# Dual-VCA.net
KiCad netlist of a schematic drawn in EAGLE
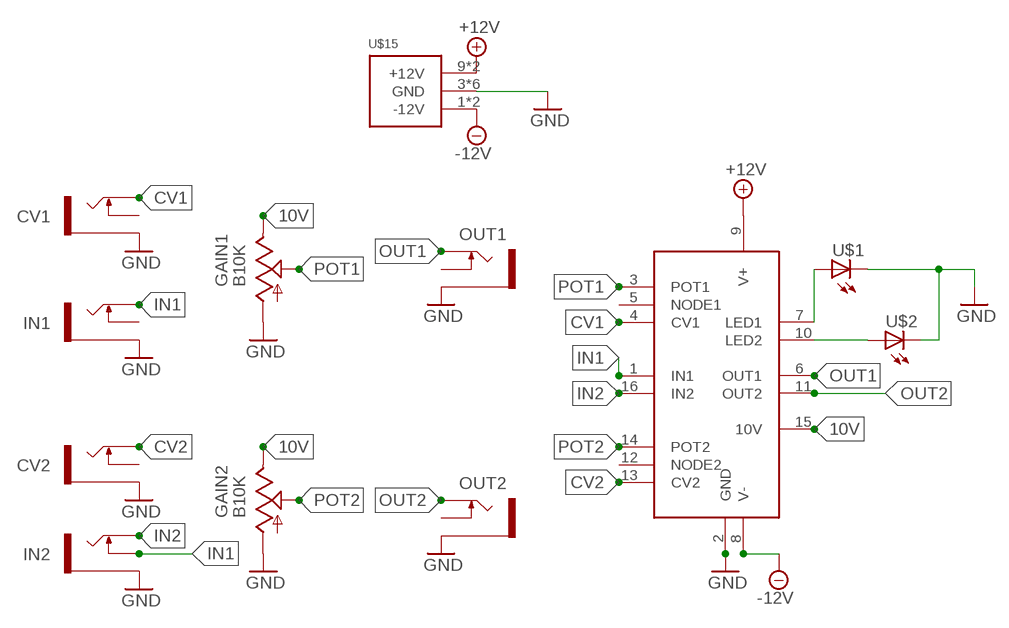
[diagram p0: schematic, sheet 1]

(export (version "E")
  (design (tool "Eeschema 10.0.6"))
  (components
    (comp (ref "CV1")
      (value "THONKICONN-SOCKETS-PJ301M-12NEW")
      (footprint "eagle-import:THONKICONN-SOCKETS-PJ301M-12")
      (fields (field (name "USE") "CV1"))
      (libsource (lib "eagle-import") (part "THONKICONN-SOCKETS-PJ301M-12NEW"))
    )
    (comp (ref "CV2")
      (value "THONKICONN-SOCKETS-PJ301M-12NEW")
      (footprint "eagle-import:THONKICONN-SOCKETS-PJ301M-12")
      (fields (field (name "USE") "CV2"))
      (libsource (lib "eagle-import") (part "THONKICONN-SOCKETS-PJ301M-12NEW"))
    )
    (comp (ref "GAIN1")
      (value "B10K")
      (footprint "eagle-import:MUSICTHINGMODULAR_9MM_SNAP-IN_POT")
      (libsource (lib "eagle-import") (part "MUSICTHINGMODULAR_9MM_SNAP-IN_POT_"))
    )
    (comp (ref "GAIN2")
      (value "B10K")
      (footprint "eagle-import:MUSICTHINGMODULAR_9MM_SNAP-IN_POT")
      (libsource (lib "eagle-import") (part "MUSICTHINGMODULAR_9MM_SNAP-IN_POT_"))
    )
    (comp (ref "IN1")
      (value "THONKICONN-SOCKETS-PJ301M-12NEW")
      (footprint "eagle-import:THONKICONN-SOCKETS-PJ301M-12")
      (fields (field (name "USE") "IN1"))
      (libsource (lib "eagle-import") (part "THONKICONN-SOCKETS-PJ301M-12NEW"))
    )
    (comp (ref "IN2")
      (value "THONKICONN-SOCKETS-PJ301M-12NEW")
      (footprint "eagle-import:THONKICONN-SOCKETS-PJ301M-12")
      (fields (field (name "USE") "IN2"))
      (libsource (lib "eagle-import") (part "THONKICONN-SOCKETS-PJ301M-12NEW"))
    )
    (comp (ref "OUT1")
      (value "THONKICONN-SOCKETS-PJ301M-12NEW")
      (footprint "eagle-import:THONKICONN-SOCKETS-PJ301M-12")
      (fields (field (name "USE") "OUT1"))
      (libsource (lib "eagle-import") (part "THONKICONN-SOCKETS-PJ301M-12NEW"))
    )
    (comp (ref "OUT2")
      (value "THONKICONN-SOCKETS-PJ301M-12NEW")
      (footprint "eagle-import:THONKICONN-SOCKETS-PJ301M-12")
      (fields (field (name "USE") "OUT2"))
      (libsource (lib "eagle-import") (part "THONKICONN-SOCKETS-PJ301M-12NEW"))
    )
    (comp (ref "U$1")
      (value "LED3MM")
      (footprint "eagle-import:LED3MM")
      (libsource (lib "eagle-import") (part "LED3MM"))
    )
    (comp (ref "U$2")
      (value "LED3MM")
      (footprint "eagle-import:LED3MM")
      (libsource (lib "eagle-import") (part "LED3MM"))
    )
    (comp (ref "U$15")
      (value "POWER_SIMPLE10")
      (footprint "eagle-import:POWER_10")
      (libsource (lib "eagle-import") (part "POWER_SIMPLE10"))
    )
    (comp (ref "U1")
      (value "ES_2164_V2")
      (footprint "eagle-import:ES_2164_V2")
      (libsource (lib "eagle-import") (part "ES_2164_V2"))
    )
  )
  (nets
    (net (code "1") (name "+12V") (class "Default")
      (node (ref "U$15") (pin "10") (pinfunction "+12V_10") (pintype "bidirectional"))
      (node (ref "U$15") (pin "9") (pinfunction "+12V_9") (pintype "bidirectional"))
      (node (ref "U1") (pin "9") (pinfunction "V+_9") (pintype "bidirectional"))
    )
    (net (code "2") (name "-12V") (class "Default")
      (node (ref "U$15") (pin "1") (pinfunction "-12V_1") (pintype "bidirectional"))
      (node (ref "U$15") (pin "2") (pinfunction "-12V_2") (pintype "bidirectional"))
      (node (ref "U1") (pin "8") (pinfunction "V-_8") (pintype "bidirectional"))
    )
    (net (code "3") (name "10V") (class "Default")
      (node (ref "GAIN1") (pin "3") (pinfunction "E_3") (pintype "passive"))
      (node (ref "GAIN2") (pin "3") (pinfunction "E_3") (pintype "passive"))
      (node (ref "U1") (pin "15") (pinfunction "10V_15") (pintype "bidirectional"))
    )
    (net (code "4") (name "CV1") (class "Default")
      (node (ref "CV1") (pin "P$1_TIP") (pinfunction "TIP_P$1_TIP") (pintype "passive"))
      (node (ref "U1") (pin "4") (pinfunction "CV1_4") (pintype "bidirectional"))
    )
    (net (code "5") (name "CV2") (class "Default")
      (node (ref "CV2") (pin "P$1_TIP") (pinfunction "TIP_P$1_TIP") (pintype "passive"))
      (node (ref "U1") (pin "13") (pinfunction "CV2_13") (pintype "bidirectional"))
    )
    (net (code "6") (name "GND") (class "Default")
      (node (ref "CV1") (pin "P$3_SLEEVE") (pinfunction "SLEEVE_P$3_SLEEVE") (pintype "passive"))
      (node (ref "CV2") (pin "P$3_SLEEVE") (pinfunction "SLEEVE_P$3_SLEEVE") (pintype "passive"))
      (node (ref "GAIN1") (pin "1") (pinfunction "A_1") (pintype "passive"))
      (node (ref "GAIN2") (pin "1") (pinfunction "A_1") (pintype "passive"))
      (node (ref "IN1") (pin "P$3_SLEEVE") (pinfunction "SLEEVE_P$3_SLEEVE") (pintype "passive"))
      (node (ref "IN2") (pin "P$3_SLEEVE") (pinfunction "SLEEVE_P$3_SLEEVE") (pintype "passive"))
      (node (ref "OUT1") (pin "P$3_SLEEVE") (pinfunction "SLEEVE_P$3_SLEEVE") (pintype "passive"))
      (node (ref "OUT2") (pin "P$3_SLEEVE") (pinfunction "SLEEVE_P$3_SLEEVE") (pintype "passive"))
      (node (ref "U$1") (pin "K") (pinfunction "C_K") (pintype "passive"))
      (node (ref "U$15") (pin "3") (pinfunction "GND_3") (pintype "bidirectional"))
      (node (ref "U$15") (pin "4") (pinfunction "GND_4") (pintype "bidirectional"))
      (node (ref "U$15") (pin "5") (pinfunction "GND_5") (pintype "bidirectional"))
      (node (ref "U$15") (pin "6") (pinfunction "GND_6") (pintype "bidirectional"))
      (node (ref "U$15") (pin "7") (pinfunction "GND_7") (pintype "bidirectional"))
      (node (ref "U$15") (pin "8") (pinfunction "GND_8") (pintype "bidirectional"))
      (node (ref "U$2") (pin "K") (pinfunction "C_K") (pintype "passive"))
      (node (ref "U1") (pin "2") (pinfunction "GND_2") (pintype "bidirectional"))
    )
    (net (code "7") (name "IN1") (class "Default")
      (node (ref "IN1") (pin "P$1_TIP") (pinfunction "TIP_P$1_TIP") (pintype "passive"))
      (node (ref "IN2") (pin "P$2_SWITCH") (pinfunction "SWITCH_P$2_SWITCH") (pintype "passive"))
      (node (ref "U1") (pin "1") (pinfunction "IN1_1") (pintype "bidirectional"))
    )
    (net (code "8") (name "IN2") (class "Default")
      (node (ref "IN2") (pin "P$1_TIP") (pinfunction "TIP_P$1_TIP") (pintype "passive"))
      (node (ref "U1") (pin "16") (pinfunction "IN2_16") (pintype "bidirectional"))
    )
    (net (code "9") (name "Net-(U1-LED1)") (class "Default")
      (node (ref "U$1") (pin "A") (pinfunction "A_A") (pintype "passive"))
      (node (ref "U1") (pin "7") (pinfunction "LED1_7") (pintype "bidirectional"))
    )
    (net (code "10") (name "Net-(U1-LED2)") (class "Default")
      (node (ref "U$2") (pin "A") (pinfunction "A_A") (pintype "passive"))
      (node (ref "U1") (pin "10") (pinfunction "LED2_10") (pintype "bidirectional"))
    )
    (net (code "11") (name "OUT1") (class "Default")
      (node (ref "OUT1") (pin "P$1_TIP") (pinfunction "TIP_P$1_TIP") (pintype "passive"))
      (node (ref "U1") (pin "6") (pinfunction "OUT1_6") (pintype "bidirectional"))
    )
    (net (code "12") (name "OUT2") (class "Default")
      (node (ref "OUT2") (pin "P$1_TIP") (pinfunction "TIP_P$1_TIP") (pintype "passive"))
      (node (ref "U1") (pin "11") (pinfunction "OUT2_11") (pintype "bidirectional"))
    )
    (net (code "13") (name "POT1") (class "Default")
      (node (ref "GAIN1") (pin "2") (pinfunction "S_2") (pintype "passive"))
      (node (ref "U1") (pin "3") (pinfunction "POT1_3") (pintype "bidirectional"))
    )
    (net (code "14") (name "POT2") (class "Default")
      (node (ref "GAIN2") (pin "2") (pinfunction "S_2") (pintype "passive"))
      (node (ref "U1") (pin "14") (pinfunction "POT2_14") (pintype "bidirectional"))
    )
    (net (code "15") (name "unconnected-(CV1-SWITCH-PadP$2_SWITCH)") (class "Default")
      (node (ref "CV1") (pin "P$2_SWITCH") (pinfunction "SWITCH_P$2_SWITCH") (pintype "passive"))
    )
    (net (code "16") (name "unconnected-(CV2-SWITCH-PadP$2_SWITCH)") (class "Default")
      (node (ref "CV2") (pin "P$2_SWITCH") (pinfunction "SWITCH_P$2_SWITCH") (pintype "passive"))
    )
    (net (code "17") (name "unconnected-(IN1-SWITCH-PadP$2_SWITCH)") (class "Default")
      (node (ref "IN1") (pin "P$2_SWITCH") (pinfunction "SWITCH_P$2_SWITCH") (pintype "passive"))
    )
    (net (code "18") (name "unconnected-(OUT1-SWITCH-PadP$2_SWITCH)") (class "Default")
      (node (ref "OUT1") (pin "P$2_SWITCH") (pinfunction "SWITCH_P$2_SWITCH") (pintype "passive"))
    )
    (net (code "19") (name "unconnected-(OUT2-SWITCH-PadP$2_SWITCH)") (class "Default")
      (node (ref "OUT2") (pin "P$2_SWITCH") (pinfunction "SWITCH_P$2_SWITCH") (pintype "passive"))
    )
    (net (code "20") (name "unconnected-(U1-NODE1-Pad5)") (class "Default")
      (node (ref "U1") (pin "5") (pinfunction "NODE1_5") (pintype "bidirectional"))
    )
    (net (code "21") (name "unconnected-(U1-NODE2-Pad12)") (class "Default")
      (node (ref "U1") (pin "12") (pinfunction "NODE2_12") (pintype "bidirectional"))
    )
  )
)
